# ElectromagnetLevitationTest.net
KiCad netlist of a schematic drawn in EAGLE
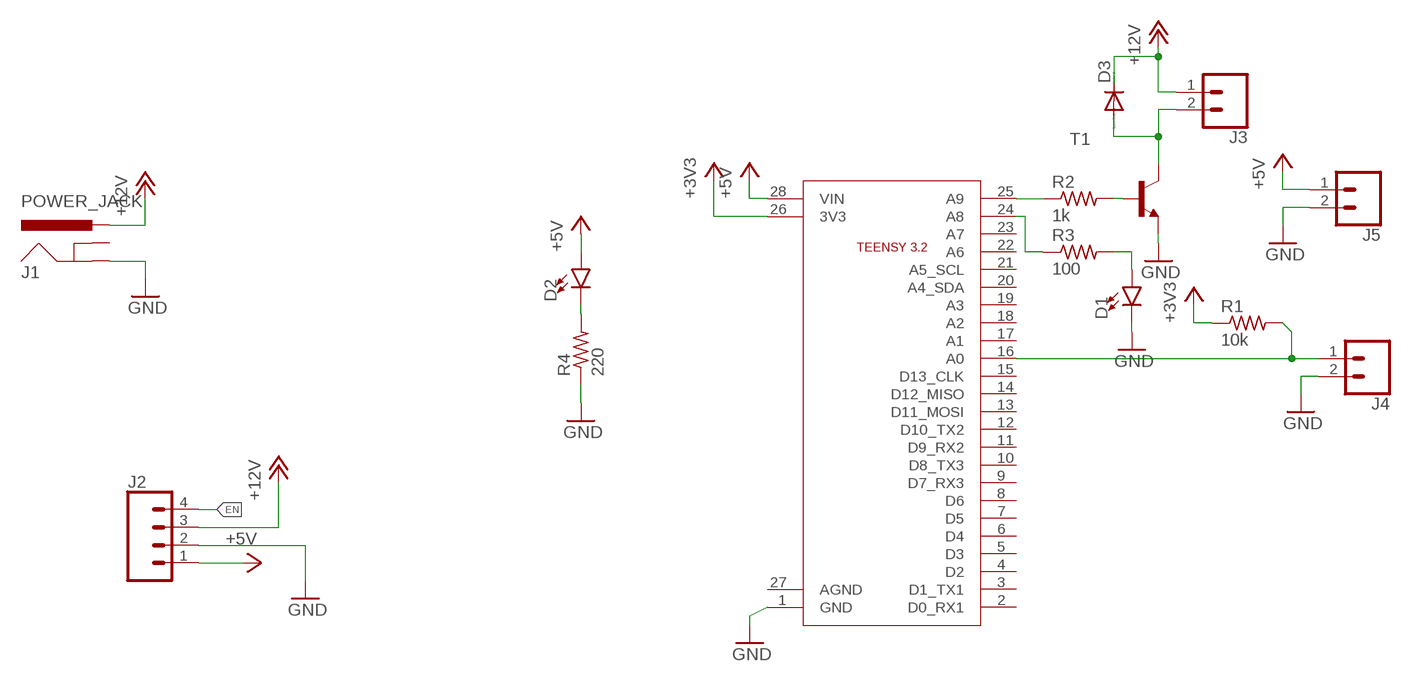
[diagram p0: schematic, sheet 1]

(export (version "E")
  (design (tool "Eeschema 10.0.6"))
  (components
    (comp (ref "D1")
      (value "LED5MM")
      (footprint "eagle-import:LED_5MM")
      (libsource (lib "eagle-import") (part "LED5MM"))
    )
    (comp (ref "D2")
      (value "LED5MM")
      (footprint "eagle-import:LED_5MM")
      (libsource (lib "eagle-import") (part "LED5MM"))
    )
    (comp (ref "D3")
      (value "DIODE-D-7.5")
      (footprint "eagle-import:D-7.5")
      (libsource (lib "eagle-import") (part "DIODE-D-7.5"))
    )
    (comp (ref "J1")
      (value "POWER_JACK")
      (footprint "eagle-import:POWER_JACK_PTH")
      (libsource (lib "eagle-import") (part "POWER_JACK"))
    )
    (comp (ref "J2")
      (value "CONN_04")
      (footprint "eagle-import:1X04")
      (libsource (lib "eagle-import") (part "CONN_04"))
    )
    (comp (ref "J3")
      (value "CONN_023.5MM")
      (footprint "eagle-import:SCREWTERMINAL-3.5MM-2")
      (libsource (lib "eagle-import") (part "CONN_023.5MM"))
    )
    (comp (ref "J4")
      (value "CONN_023.5MM")
      (footprint "eagle-import:SCREWTERMINAL-3.5MM-2")
      (libsource (lib "eagle-import") (part "CONN_023.5MM"))
    )
    (comp (ref "J5")
      (value "CONN_023.5MM")
      (footprint "eagle-import:SCREWTERMINAL-3.5MM-2")
      (libsource (lib "eagle-import") (part "CONN_023.5MM"))
    )
    (comp (ref "R1")
      (value "10k")
      (footprint "eagle-import:0204_7")
      (libsource (lib "eagle-import") (part "R-US_0204/7"))
    )
    (comp (ref "R2")
      (value "1k")
      (footprint "eagle-import:0204_7")
      (libsource (lib "eagle-import") (part "R-US_0204/7"))
    )
    (comp (ref "R3")
      (value "100")
      (footprint "eagle-import:0204_7")
      (libsource (lib "eagle-import") (part "R-US_0204/7"))
    )
    (comp (ref "R4")
      (value "220")
      (footprint "eagle-import:0204_7")
      (libsource (lib "eagle-import") (part "R-US_0204/7"))
    )
    (comp (ref "T1")
      (value "-NPN-TO220V")
      (footprint "eagle-import:TO220V")
      (libsource (lib "eagle-import") (part "-NPN-TO220V"))
    )
    (comp (ref "U$1")
      (value "TEENSY3.2")
      (footprint "eagle-import:TEENSY")
      (libsource (lib "eagle-import") (part "TEENSY3.2"))
    )
  )
  (nets
    (net (code "1") (name "+3V3") (class "Default")
      (node (ref "R1") (pin "1") (pinfunction "1_1") (pintype "passive"))
      (node (ref "U$1") (pin "26") (pinfunction "3V3_26") (pintype "bidirectional"))
    )
    (net (code "2") (name "+5V") (class "Default")
      (node (ref "D2") (pin "A") (pinfunction "A_A") (pintype "passive"))
      (node (ref "J2") (pin "1") (pinfunction "1_1") (pintype "passive"))
      (node (ref "J5") (pin "1") (pinfunction "1_1") (pintype "passive"))
      (node (ref "U$1") (pin "28") (pinfunction "VIN_28") (pintype "bidirectional"))
    )
    (net (code "3") (name "+12V") (class "Default")
      (node (ref "D3") (pin "C") (pinfunction "C_C") (pintype "passive"))
      (node (ref "J1") (pin "PWR") (pinfunction "PWR_PWR") (pintype "bidirectional"))
      (node (ref "J2") (pin "3") (pinfunction "3_3") (pintype "passive"))
      (node (ref "J3") (pin "1") (pinfunction "1_1") (pintype "passive"))
    )
    (net (code "4") (name "EN") (class "Default")
      (node (ref "J2") (pin "4") (pinfunction "4_4") (pintype "passive"))
    )
    (net (code "5") (name "GND") (class "Default")
      (node (ref "D1") (pin "K") (pinfunction "C_K") (pintype "passive"))
      (node (ref "J1") (pin "GND") (pinfunction "GND_GND") (pintype "bidirectional"))
      (node (ref "J2") (pin "2") (pinfunction "2_2") (pintype "passive"))
      (node (ref "J4") (pin "2") (pinfunction "2_2") (pintype "passive"))
      (node (ref "J5") (pin "2") (pinfunction "2_2") (pintype "passive"))
      (node (ref "R4") (pin "1") (pinfunction "1_1") (pintype "passive"))
      (node (ref "T1") (pin "3") (pinfunction "E_3") (pintype "passive"))
      (node (ref "U$1") (pin "1") (pinfunction "GND_1") (pintype "bidirectional"))
    )
    (net (code "6") (name "Net-(D1-PadA)") (class "Default")
      (node (ref "D1") (pin "A") (pinfunction "A_A") (pintype "passive"))
      (node (ref "R3") (pin "2") (pinfunction "2_2") (pintype "passive"))
    )
    (net (code "7") (name "Net-(D2-C)") (class "Default")
      (node (ref "D2") (pin "K") (pinfunction "C_K") (pintype "passive"))
      (node (ref "R4") (pin "2") (pinfunction "2_2") (pintype "passive"))
    )
    (net (code "8") (name "Net-(T1-B)") (class "Default")
      (node (ref "R2") (pin "2") (pinfunction "2_2") (pintype "passive"))
      (node (ref "T1") (pin "1") (pinfunction "B_1") (pintype "passive"))
    )
    (net (code "9") (name "Net-(T1-C)") (class "Default")
      (node (ref "D3") (pin "A") (pinfunction "A_A") (pintype "passive"))
      (node (ref "J3") (pin "2") (pinfunction "2_2") (pintype "passive"))
      (node (ref "T1") (pin "2") (pinfunction "C_2") (pintype "passive"))
    )
    (net (code "10") (name "Net-(U$1-A0)") (class "Default")
      (node (ref "J4") (pin "1") (pinfunction "1_1") (pintype "passive"))
      (node (ref "R1") (pin "2") (pinfunction "2_2") (pintype "passive"))
      (node (ref "U$1") (pin "16") (pinfunction "A0_16") (pintype "bidirectional"))
    )
    (net (code "11") (name "Net-(U$1-A8)") (class "Default")
      (node (ref "R3") (pin "1") (pinfunction "1_1") (pintype "passive"))
      (node (ref "U$1") (pin "24") (pinfunction "A8_24") (pintype "bidirectional"))
    )
    (net (code "12") (name "Net-(U$1-A9)") (class "Default")
      (node (ref "R2") (pin "1") (pinfunction "1_1") (pintype "passive"))
      (node (ref "U$1") (pin "25") (pinfunction "A9_25") (pintype "bidirectional"))
    )
    (net (code "13") (name "unconnected-(J1-PadGNDBREAK)") (class "Default")
      (node (ref "J1") (pin "GNDBREAK") (pinfunction "GNDBREAK_GNDBREAK") (pintype "bidirectional"))
    )
    (net (code "14") (name "unconnected-(U$1-A1-Pad17)") (class "Default")
      (node (ref "U$1") (pin "17") (pinfunction "A1_17") (pintype "bidirectional"))
    )
    (net (code "15") (name "unconnected-(U$1-A2-Pad18)") (class "Default")
      (node (ref "U$1") (pin "18") (pinfunction "A2_18") (pintype "bidirectional"))
    )
    (net (code "16") (name "unconnected-(U$1-A3-Pad19)") (class "Default")
      (node (ref "U$1") (pin "19") (pinfunction "A3_19") (pintype "bidirectional"))
    )
    (net (code "17") (name "unconnected-(U$1-A4_SDA-Pad20)") (class "Default")
      (node (ref "U$1") (pin "20") (pinfunction "A4_SDA_20") (pintype "bidirectional"))
    )
    (net (code "18") (name "unconnected-(U$1-A5_SCL-Pad21)") (class "Default")
      (node (ref "U$1") (pin "21") (pinfunction "A5_SCL_21") (pintype "bidirectional"))
    )
    (net (code "19") (name "unconnected-(U$1-A6-Pad22)") (class "Default")
      (node (ref "U$1") (pin "22") (pinfunction "A6_22") (pintype "bidirectional"))
    )
    (net (code "20") (name "unconnected-(U$1-A7-Pad23)") (class "Default")
      (node (ref "U$1") (pin "23") (pinfunction "A7_23") (pintype "bidirectional"))
    )
    (net (code "21") (name "unconnected-(U$1-AGND-Pad27)") (class "Default")
      (node (ref "U$1") (pin "27") (pinfunction "AGND_27") (pintype "bidirectional"))
    )
    (net (code "22") (name "unconnected-(U$1-D0_RX1-Pad2)") (class "Default")
      (node (ref "U$1") (pin "2") (pinfunction "D0_RX1_2") (pintype "bidirectional"))
    )
    (net (code "23") (name "unconnected-(U$1-D1_TX1-Pad3)") (class "Default")
      (node (ref "U$1") (pin "3") (pinfunction "D1_TX1_3") (pintype "bidirectional"))
    )
    (net (code "24") (name "unconnected-(U$1-D2-Pad4)") (class "Default")
      (node (ref "U$1") (pin "4") (pinfunction "D2_4") (pintype "bidirectional"))
    )
    (net (code "25") (name "unconnected-(U$1-D3-Pad5)") (class "Default")
      (node (ref "U$1") (pin "5") (pinfunction "D3_5") (pintype "bidirectional"))
    )
    (net (code "26") (name "unconnected-(U$1-D4-Pad6)") (class "Default")
      (node (ref "U$1") (pin "6") (pinfunction "D4_6") (pintype "bidirectional"))
    )
    (net (code "27") (name "unconnected-(U$1-D5-Pad7)") (class "Default")
      (node (ref "U$1") (pin "7") (pinfunction "D5_7") (pintype "bidirectional"))
    )
    (net (code "28") (name "unconnected-(U$1-D6-Pad8)") (class "Default")
      (node (ref "U$1") (pin "8") (pinfunction "D6_8") (pintype "bidirectional"))
    )
    (net (code "29") (name "unconnected-(U$1-D7_RX3-Pad9)") (class "Default")
      (node (ref "U$1") (pin "9") (pinfunction "D7_RX3_9") (pintype "bidirectional"))
    )
    (net (code "30") (name "unconnected-(U$1-D8_TX3-Pad10)") (class "Default")
      (node (ref "U$1") (pin "10") (pinfunction "D8_TX3_10") (pintype "bidirectional"))
    )
    (net (code "31") (name "unconnected-(U$1-D9_RX2-Pad11)") (class "Default")
      (node (ref "U$1") (pin "11") (pinfunction "D9_RX2_11") (pintype "bidirectional"))
    )
    (net (code "32") (name "unconnected-(U$1-D10_TX2-Pad12)") (class "Default")
      (node (ref "U$1") (pin "12") (pinfunction "D10_TX2_12") (pintype "bidirectional"))
    )
    (net (code "33") (name "unconnected-(U$1-D11_MOSI-Pad13)") (class "Default")
      (node (ref "U$1") (pin "13") (pinfunction "D11_MOSI_13") (pintype "bidirectional"))
    )
    (net (code "34") (name "unconnected-(U$1-D12_MISO-Pad14)") (class "Default")
      (node (ref "U$1") (pin "14") (pinfunction "D12_MISO_14") (pintype "bidirectional"))
    )
    (net (code "35") (name "unconnected-(U$1-D13_CLK-Pad15)") (class "Default")
      (node (ref "U$1") (pin "15") (pinfunction "D13_CLK_15") (pintype "bidirectional"))
    )
  )
)
